# schematic.net
KiCad netlist of a schematic drawn in EasyEDA
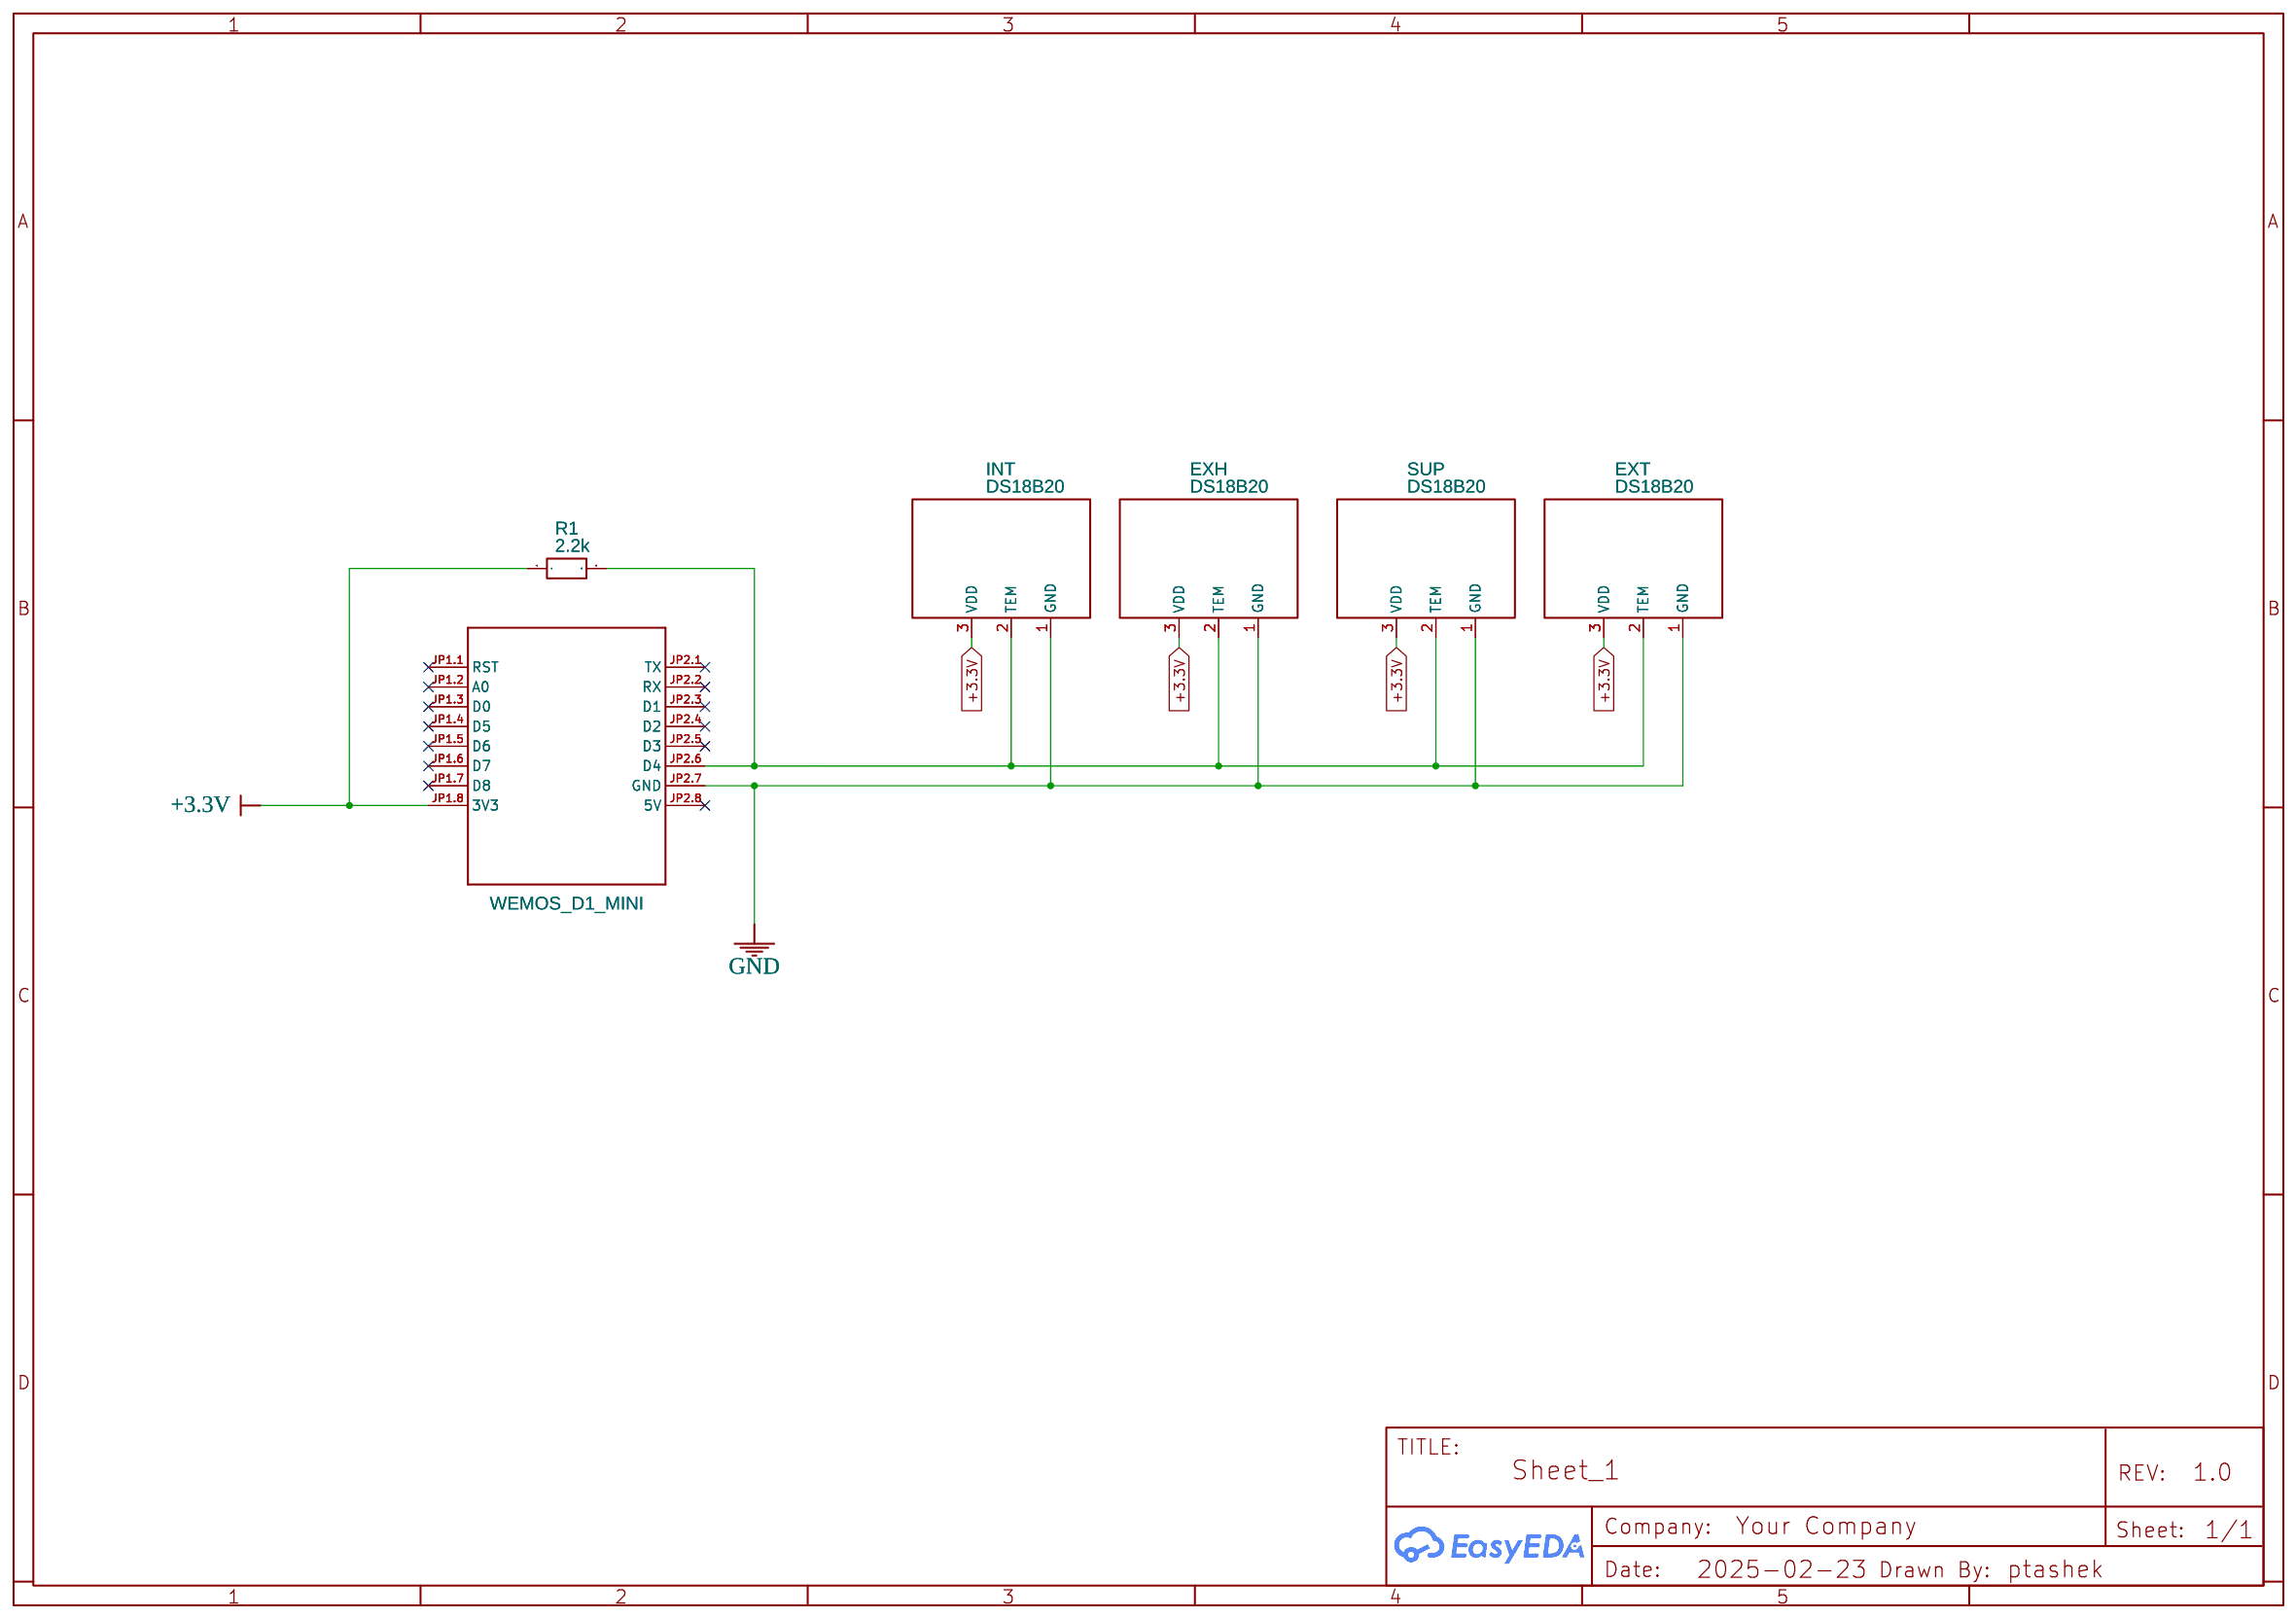
[diagram p0: schematic sheet]

(export (version "E")
  (design (tool "Eeschema 10.0.6"))
  (components
    (comp (ref "EXH") (value "DS18B20") (libsource (lib "") (part "DS18B21_2")))
    (comp (ref "EXT") (value "DS18B20") (libsource (lib "") (part "DS18B21_3")))
    (comp (ref "INT") (value "DS18B20") (libsource (lib "") (part "DS18B21_1")))
    (comp (ref "R1")
      (value "2.2k")
      (fields
        (field (name "Manufacturer Part") "CR2512F2K20E04Z")
        (field (name "Manufacturer") "EVER OHMS(天二科技)")
      )
      (libsource (lib "") (part "CR2512F2K20E04Z"))
    )
    (comp (ref "SUP") (value "DS18B20") (libsource (lib "") (part "DS18B21")))
    (comp (ref "WEMOS_D1_MINI")
      (value "WEMOS-D1-MINI-SHIELD")
      (libsource (lib "") (part "WEMOS-D1-MINI-SHIELD"))
    )
  )
  (nets
    (net (code "1") (name "+3.3V") (class "Default")
      (node (ref "EXH") (pin "3") (pinfunction "VDD_3") (pintype "unspecified"))
      (node (ref "EXT") (pin "3") (pinfunction "VDD_3") (pintype "unspecified"))
      (node (ref "INT") (pin "3") (pinfunction "VDD_3") (pintype "unspecified"))
      (node (ref "R1") (pin "1") (pinfunction "1_1") (pintype "unspecified"))
      (node (ref "SUP") (pin "3") (pinfunction "VDD_3") (pintype "unspecified"))
      (node (ref "WEMOS_D1_MINI") (pin "JP1.8") (pinfunction "3V3_JP1.8") (pintype "bidirectional"))
    )
    (net (code "2") (name "GND") (class "Default")
      (node (ref "EXH") (pin "1") (pinfunction "GND_1") (pintype "unspecified"))
      (node (ref "EXT") (pin "1") (pinfunction "GND_1") (pintype "unspecified"))
      (node (ref "INT") (pin "1") (pinfunction "GND_1") (pintype "unspecified"))
      (node (ref "SUP") (pin "1") (pinfunction "GND_1") (pintype "unspecified"))
      (node (ref "WEMOS_D1_MINI") (pin "JP2.7") (pinfunction "GND_JP2.7") (pintype "bidirectional"))
    )
    (net (code "3") (name "Net-(EXH-TEM)") (class "Default")
      (node (ref "EXH") (pin "2") (pinfunction "TEM_2") (pintype "unspecified"))
      (node (ref "EXT") (pin "2") (pinfunction "TEM_2") (pintype "unspecified"))
      (node (ref "INT") (pin "2") (pinfunction "TEM_2") (pintype "unspecified"))
      (node (ref "R1") (pin "2") (pinfunction "2_2") (pintype "unspecified"))
      (node (ref "SUP") (pin "2") (pinfunction "TEM_2") (pintype "unspecified"))
      (node (ref "WEMOS_D1_MINI") (pin "JP2.6") (pinfunction "D4_JP2.6") (pintype "bidirectional"))
    )
    (net (code "4") (name "unconnected-(WEMOS_D1_MINI-5V-PadJP2.8)") (class "Default")
      (node (ref "WEMOS_D1_MINI") (pin "JP2.8") (pinfunction "5V_JP2.8") (pintype "bidirectional+no_connect"))
    )
    (net (code "5") (name "unconnected-(WEMOS_D1_MINI-A0-PadJP1.2)") (class "Default")
      (node (ref "WEMOS_D1_MINI") (pin "JP1.2") (pinfunction "A0_JP1.2") (pintype "bidirectional+no_connect"))
    )
    (net (code "6") (name "unconnected-(WEMOS_D1_MINI-D0-PadJP1.3)") (class "Default")
      (node (ref "WEMOS_D1_MINI") (pin "JP1.3") (pinfunction "D0_JP1.3") (pintype "bidirectional+no_connect"))
    )
    (net (code "7") (name "unconnected-(WEMOS_D1_MINI-D1-PadJP2.3)") (class "Default")
      (node (ref "WEMOS_D1_MINI") (pin "JP2.3") (pinfunction "D1_JP2.3") (pintype "bidirectional+no_connect"))
    )
    (net (code "8") (name "unconnected-(WEMOS_D1_MINI-D2-PadJP2.4)") (class "Default")
      (node (ref "WEMOS_D1_MINI") (pin "JP2.4") (pinfunction "D2_JP2.4") (pintype "bidirectional+no_connect"))
    )
    (net (code "9") (name "unconnected-(WEMOS_D1_MINI-D3-PadJP2.5)") (class "Default")
      (node (ref "WEMOS_D1_MINI") (pin "JP2.5") (pinfunction "D3_JP2.5") (pintype "bidirectional+no_connect"))
    )
    (net (code "10") (name "unconnected-(WEMOS_D1_MINI-D5-PadJP1.4)") (class "Default")
      (node (ref "WEMOS_D1_MINI") (pin "JP1.4") (pinfunction "D5_JP1.4") (pintype "bidirectional+no_connect"))
    )
    (net (code "11") (name "unconnected-(WEMOS_D1_MINI-D6-PadJP1.5)") (class "Default")
      (node (ref "WEMOS_D1_MINI") (pin "JP1.5") (pinfunction "D6_JP1.5") (pintype "bidirectional+no_connect"))
    )
    (net (code "12") (name "unconnected-(WEMOS_D1_MINI-D7-PadJP1.6)") (class "Default")
      (node (ref "WEMOS_D1_MINI") (pin "JP1.6") (pinfunction "D7_JP1.6") (pintype "bidirectional+no_connect"))
    )
    (net (code "13") (name "unconnected-(WEMOS_D1_MINI-D8-PadJP1.7)") (class "Default")
      (node (ref "WEMOS_D1_MINI") (pin "JP1.7") (pinfunction "D8_JP1.7") (pintype "bidirectional+no_connect"))
    )
    (net (code "14") (name "unconnected-(WEMOS_D1_MINI-RST-PadJP1.1)") (class "Default")
      (node (ref "WEMOS_D1_MINI") (pin "JP1.1") (pinfunction "RST_JP1.1") (pintype "bidirectional+no_connect"))
    )
    (net (code "15") (name "unconnected-(WEMOS_D1_MINI-RX-PadJP2.2)") (class "Default")
      (node (ref "WEMOS_D1_MINI") (pin "JP2.2") (pinfunction "RX_JP2.2") (pintype "bidirectional+no_connect"))
    )
    (net (code "16") (name "unconnected-(WEMOS_D1_MINI-TX-PadJP2.1)") (class "Default")
      (node (ref "WEMOS_D1_MINI") (pin "JP2.1") (pinfunction "TX_JP2.1") (pintype "bidirectional+no_connect"))
    )
  )
)
